# ProPrj_TO-56_Laser_Simple_4_Pin_Mount_20.net
KiCad netlist of a schematic drawn in EasyEDA Pro
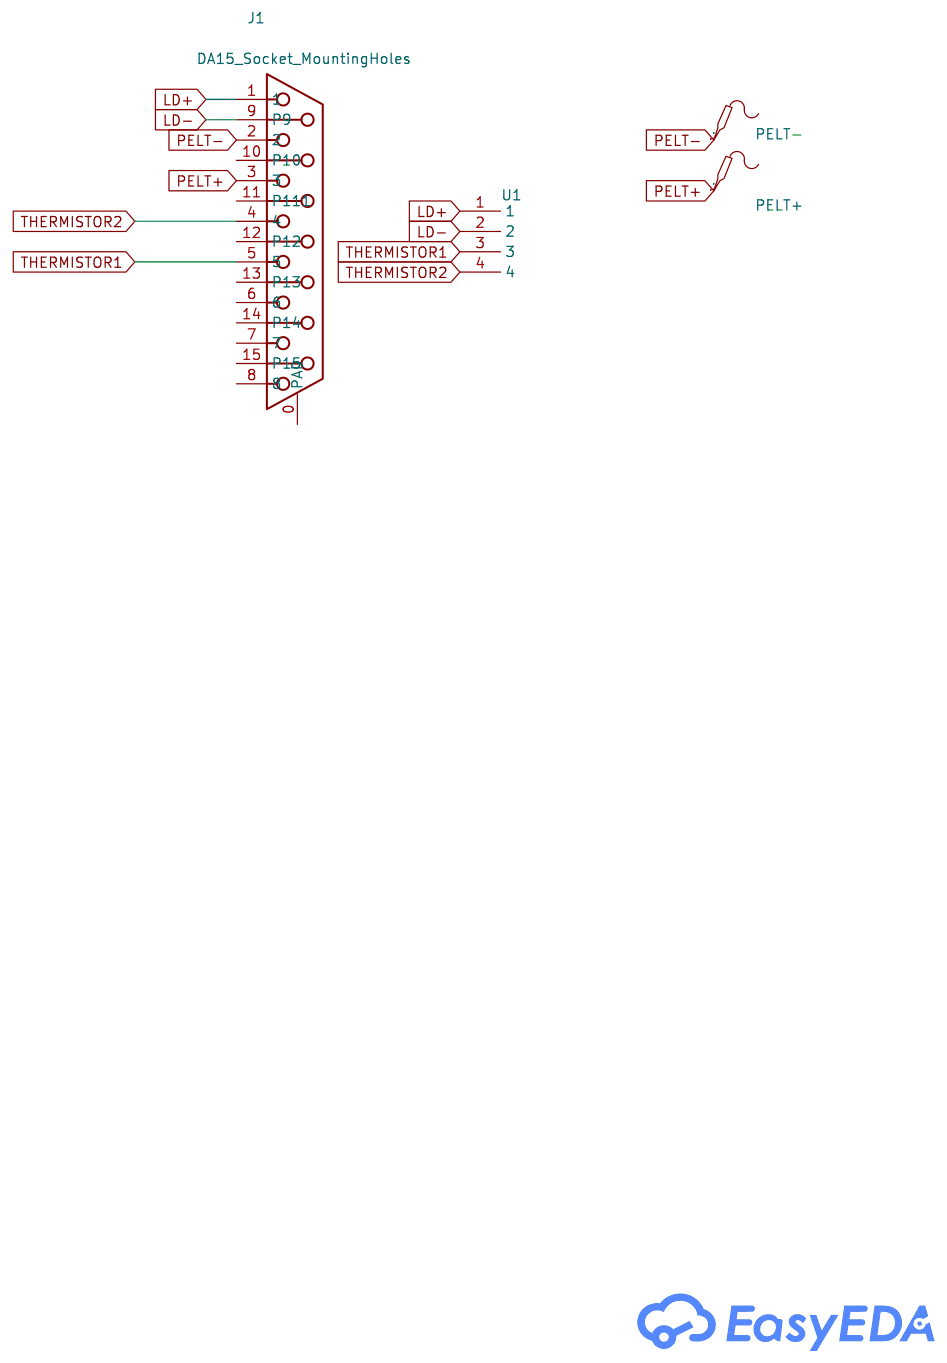
[diagram p0: schematic sheet]

(export (version "E")
  (design (tool "Eeschema 10.0.6"))
  (components
    (comp (ref "J1")
      (value "DA15_Socket_MountingHoles")
      (footprint "easyedapro:Connector_Dsub:DSUB-15_Socket_Vertical_P2.77x2.84mm_MountingHoles")
      (description "15-pin D-SUB connector, socket (female) (low-density/2 columns), Mounting Hole")
      (libsource (lib "easyedapro") (part "Connector_DA15_Socket_MountingHoles"))
    )
    (comp (ref "PELT+")
      (value "~")
      (footprint "easyedapro:Test-Point-0.5mm")
      (description "Test-Point")
      (libsource (lib "easyedapro") (part "Test-Point"))
    )
    (comp (ref "PELT-")
      (value "~")
      (footprint "easyedapro:Test-Point-0.5mm")
      (description "Test-Point")
      (libsource (lib "easyedapro") (part "Test-Point"))
    )
    (comp (ref "U1") (value "~") (footprint "easyedapro:TO56") (libsource (lib "easyedapro") (part "TO56")))
  )
  (nets
    (net (code "1") (name "LD+") (class "Default")
      (node (ref "J1") (pin "1") (pinfunction "1_1") (pintype "unspecified"))
      (node (ref "U1") (pin "1") (pinfunction "1_1") (pintype "input"))
    )
    (net (code "2") (name "LD-") (class "Default")
      (node (ref "J1") (pin "9") (pinfunction "P9_9") (pintype "unspecified"))
      (node (ref "U1") (pin "2") (pinfunction "2_2") (pintype "input"))
    )
    (net (code "3") (name "PELT+") (class "Default")
      (node (ref "J1") (pin "3") (pinfunction "3_3") (pintype "unspecified"))
      (node (ref "PELT+") (pin "1") (pinfunction "1_1") (pintype "input"))
    )
    (net (code "4") (name "PELT-") (class "Default")
      (node (ref "J1") (pin "2") (pinfunction "2_2") (pintype "unspecified"))
      (node (ref "PELT-") (pin "1") (pinfunction "1_1") (pintype "input"))
    )
    (net (code "5") (name "THERMISTOR1") (class "Default")
      (node (ref "J1") (pin "5") (pinfunction "5_5") (pintype "unspecified"))
      (node (ref "U1") (pin "3") (pinfunction "3_3") (pintype "input"))
    )
    (net (code "6") (name "THERMISTOR2") (class "Default")
      (node (ref "J1") (pin "4") (pinfunction "4_4") (pintype "unspecified"))
      (node (ref "U1") (pin "4") (pinfunction "4_4") (pintype "input"))
    )
    (net (code "7") (name "unconnected-(J1-P10-Pad10)") (class "Default")
      (node (ref "J1") (pin "10") (pinfunction "P10_10") (pintype "unspecified"))
    )
    (net (code "8") (name "unconnected-(J1-P12-Pad12)") (class "Default")
      (node (ref "J1") (pin "12") (pinfunction "P12_12") (pintype "unspecified"))
    )
    (net (code "9") (name "unconnected-(J1-P13-Pad13)") (class "Default")
      (node (ref "J1") (pin "13") (pinfunction "P13_13") (pintype "unspecified"))
    )
    (net (code "10") (name "unconnected-(J1-P14-Pad14)") (class "Default")
      (node (ref "J1") (pin "14") (pinfunction "P14_14") (pintype "unspecified"))
    )
    (net (code "11") (name "unconnected-(J1-P15-Pad15)") (class "Default")
      (node (ref "J1") (pin "15") (pinfunction "P15_15") (pintype "unspecified"))
    )
    (net (code "12") (name "unconnected-(J1-P111-Pad11)") (class "Default")
      (node (ref "J1") (pin "11") (pinfunction "P111_11") (pintype "unspecified"))
    )
    (net (code "13") (name "unconnected-(J1-PAD-Pad0)") (class "Default")
      (node (ref "J1") (pin "0") (pinfunction "PAD_0") (pintype "unspecified"))
    )
    (net (code "14") (name "unconnected-(J1-Pad6)") (class "Default")
      (node (ref "J1") (pin "6") (pinfunction "6_6") (pintype "unspecified"))
    )
    (net (code "15") (name "unconnected-(J1-Pad7)") (class "Default")
      (node (ref "J1") (pin "7") (pinfunction "7_7") (pintype "unspecified"))
    )
    (net (code "16") (name "unconnected-(J1-Pad8)") (class "Default")
      (node (ref "J1") (pin "8") (pinfunction "8_8") (pintype "unspecified"))
    )
  )
)
